# PS3604LP.net
KiCad netlist of a schematic drawn in Altium Designer
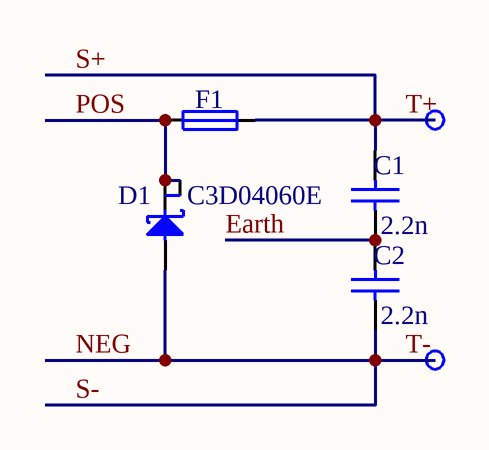
[diagram p0: PS3604LP.SchDoc]

(export (version "E")
  (design (tool "Eeschema 10.0.6"))
  (components
    (comp (ref "B1")
      (value "Plated Hole")
      (footprint "MTG420_550")
      (description "Single Terminal Socket")
      (fields (field (name "PART NUMBER") "PLATED_HOLE4.2_PAD5.5") (field (name "AUTHOR") "CERN DEM JMW"))
      (libsource (lib "Eletro-mechanical") (part "Single Terminal Socket"))
    )
    (comp (ref "B2")
      (value "Plated Hole")
      (footprint "MTG420_550")
      (description "Single Terminal Socket")
      (fields (field (name "PART NUMBER") "PLATED_HOLE4.2_PAD5.5") (field (name "AUTHOR") "CERN DEM JMW"))
      (libsource (lib "Eletro-mechanical") (part "Single Terminal Socket"))
    )
    (comp (ref "C1")
      (value "2.2n")
      (footprint "CAPC4532X250N")
      (description "Non-polarised capacitor")
      (fields
        (field (name "PART NUMBER") "CC1812_2.2NF_1000V_10%_X7R")
        (field (name "VOLTAGE") "1000V")
        (field (name "AUTHOR") "DEL")
      )
      (libsource (lib "Capacitors") (part "Capacitor - non polarized"))
    )
    (comp (ref "C2")
      (value "2.2n")
      (footprint "CAPC4532X250N")
      (description "Non-polarised capacitor")
      (fields
        (field (name "PART NUMBER") "CC1812_2.2NF_1000V_10%_X7R")
        (field (name "VOLTAGE") "1000V")
        (field (name "AUTHOR") "DEL")
      )
      (libsource (lib "Capacitors") (part "Capacitor - non polarized"))
    )
    (comp (ref "D1")
      (value "C3D04060E")
      (footprint "TO228P972X240-3N-R540X510")
      (description "Diode  Schottky Anode pin 1 and 2 cathode pin 3")
      (fields (field (name "VOLTAGE") "600V") (field (name "POWER") "7.5A") (field (name "AUTHOR") "DEL"))
      (libsource (lib "ICs And Semiconductors") (part "Diode Schottky A2_C1C3"))
    )
    (comp (ref "F1")
      (value "0.5A-125V")
      (footprint "FUSE_LITTELFUSE_0154")
      (description "Fuse")
      (fields
        (field (name "PART NUMBER") "FUSE_LITTELFUSE_0154.500DR")
        (field (name "MANUFACTURER") "LITTELFUSE")
        (field (name "AUTHOR") "CERN DEM JMW")
      )
      (libsource (lib "Eletro-mechanical") (part "Fuse"))
    )
  )
  (nets
    (net (code "1") (name "/Earth") (class "Default")
      (node (ref "C1") (pin "1") (pinfunction "1_1") (pintype "passive"))
      (node (ref "C2") (pin "2") (pinfunction "2_2") (pintype "passive"))
    )
    (net (code "2") (name "/NEG") (class "Default")
      (node (ref "B2") (pin "1") (pinfunction "1_1") (pintype "bidirectional"))
      (node (ref "C2") (pin "1") (pinfunction "1_1") (pintype "passive"))
      (node (ref "D1") (pin "2") (pinfunction "A_2") (pintype "passive"))
    )
    (net (code "3") (name "/POS") (class "Default")
      (node (ref "D1") (pin "1") (pinfunction "C_1") (pintype "passive"))
      (node (ref "D1") (pin "3") (pinfunction "A_3") (pintype "passive"))
      (node (ref "F1") (pin "1") (pinfunction "1_1") (pintype "passive"))
    )
    (net (code "4") (name "/S+") (class "Default")
      (node (ref "B1") (pin "1") (pinfunction "1_1") (pintype "bidirectional"))
      (node (ref "C1") (pin "2") (pinfunction "2_2") (pintype "passive"))
      (node (ref "F1") (pin "2") (pinfunction "2_2") (pintype "passive"))
    )
  )
)
